# Main.net
KiCad netlist of a schematic drawn in Altium Designer
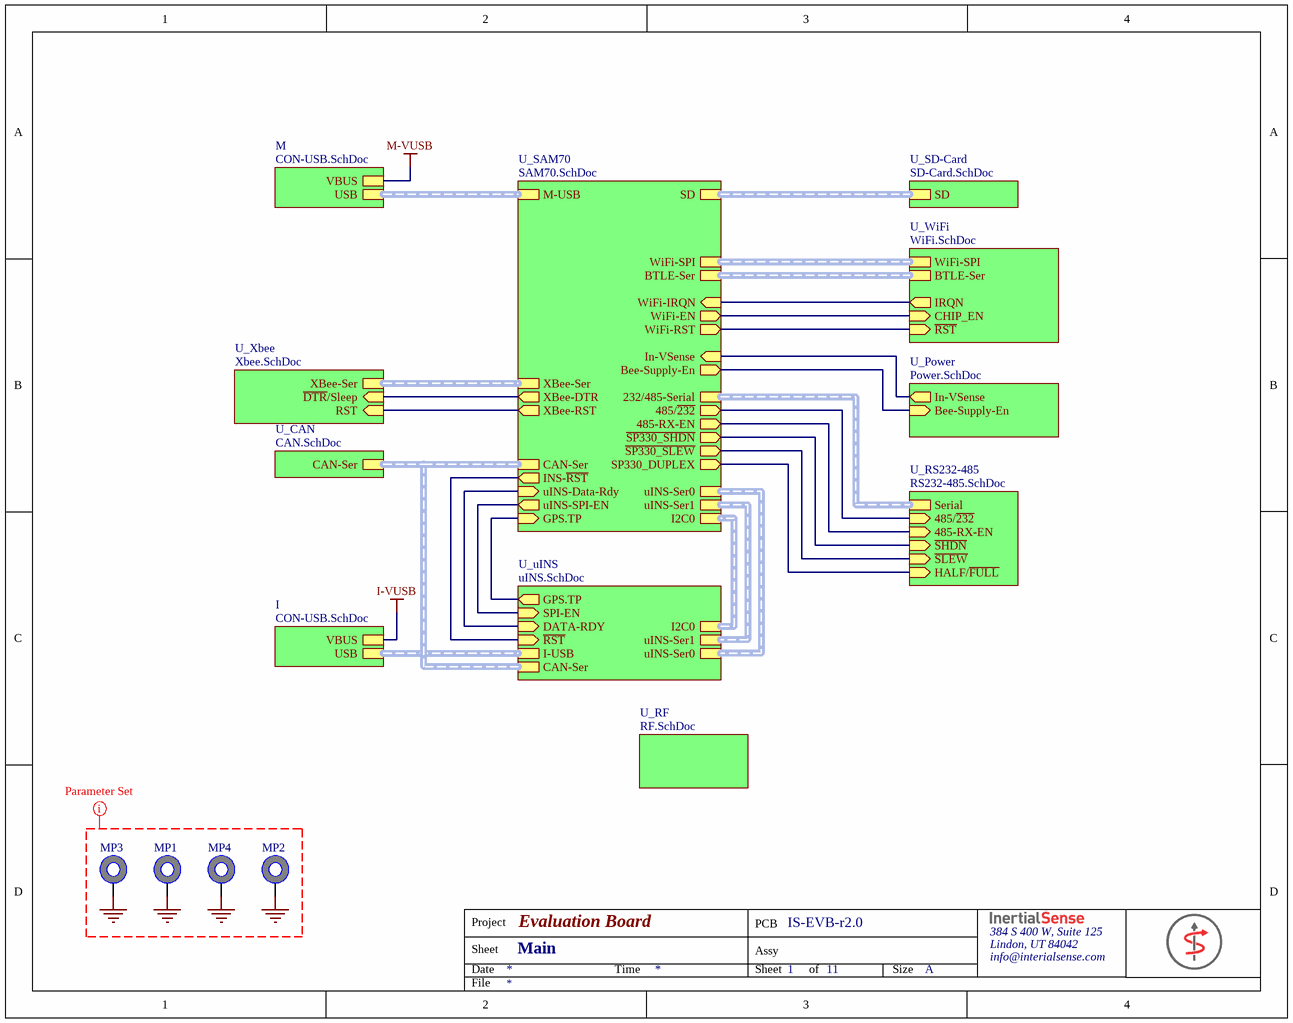
[diagram p0: Main.SchDoc]

(export (version "E")
  (design (tool "Eeschema 10.0.6"))
  (components
    (comp (ref "MP1")
      (value "Standoff")
      (footprint "9774050151R")
      (description "RND STANDOFF M2.5X0.45 STEEL 5MM")
      (fields
        (field (name "MANUFACTURER") "Wurth Electronics")
        (field (name "MANUFACTURER PART NUMBER") "9774050951R")
      )
      (libsource (lib "General") (part "Standoff"))
    )
    (comp (ref "MP2")
      (value "Standoff")
      (footprint "9774050151R")
      (description "RND STANDOFF M2.5X0.45 STEEL 5MM")
      (fields
        (field (name "MANUFACTURER") "Wurth Electronics")
        (field (name "MANUFACTURER PART NUMBER") "9774050951R")
      )
      (libsource (lib "General") (part "Standoff"))
    )
    (comp (ref "MP3")
      (value "Standoff")
      (footprint "9774050151R")
      (description "RND STANDOFF M2.5X0.45 STEEL 5MM")
      (fields
        (field (name "MANUFACTURER") "Wurth Electronics")
        (field (name "MANUFACTURER PART NUMBER") "9774050951R")
      )
      (libsource (lib "General") (part "Standoff"))
    )
    (comp (ref "MP4")
      (value "Standoff")
      (footprint "9774050151R")
      (description "RND STANDOFF M2.5X0.45 STEEL 5MM")
      (fields
        (field (name "MANUFACTURER") "Wurth Electronics")
        (field (name "MANUFACTURER PART NUMBER") "9774050951R")
      )
      (libsource (lib "General") (part "Standoff"))
    )
  )
  (nets
    (net (code "28") (name "GND") (class "Default")
      (node (ref "MP1") (pin "1") (pinfunction "1_1") (pintype "passive"))
      (node (ref "MP2") (pin "1") (pinfunction "1_1") (pintype "passive"))
      (node (ref "MP3") (pin "1") (pinfunction "1_1") (pintype "passive"))
      (node (ref "MP4") (pin "1") (pinfunction "1_1") (pintype "passive"))
    )
  )
)
